# main.net
KiCad netlist of a schematic drawn in EAGLE
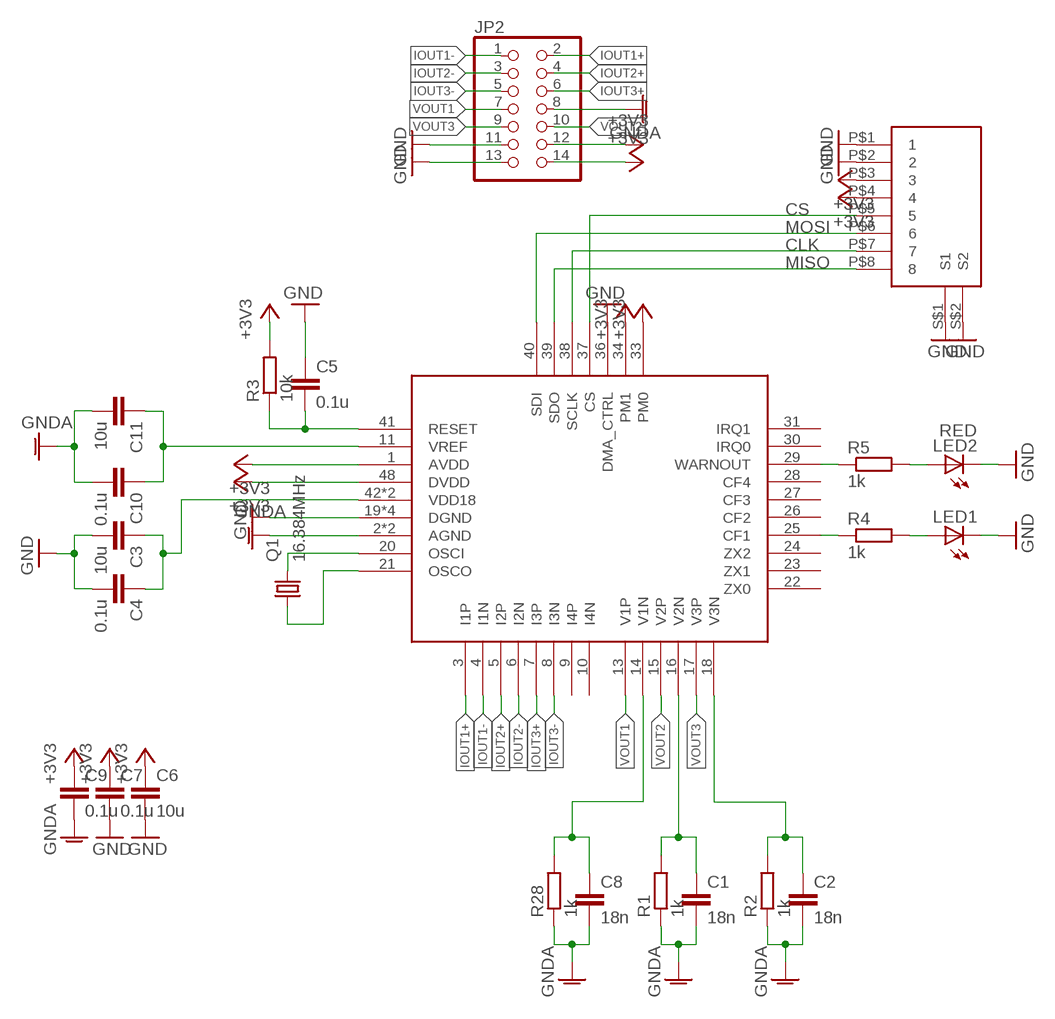
[diagram p0: schematic, sheet 1]

(export (version "E")
  (design (tool "Eeschema 10.0.6"))
  (components
    (comp (ref "C1")
      (value "18n")
      (footprint "eagle-import:C0805")
      (libsource (lib "eagle-import") (part "C-EUC0805"))
    )
    (comp (ref "C2")
      (value "18n")
      (footprint "eagle-import:C0805")
      (libsource (lib "eagle-import") (part "C-EUC0805"))
    )
    (comp (ref "C3")
      (value "10u")
      (footprint "eagle-import:C1206")
      (libsource (lib "eagle-import") (part "C-EUC1206"))
    )
    (comp (ref "C4")
      (value "0.1u")
      (footprint "eagle-import:C0805")
      (libsource (lib "eagle-import") (part "C-EUC0805"))
    )
    (comp (ref "C5")
      (value "0.1u")
      (footprint "eagle-import:C0805")
      (libsource (lib "eagle-import") (part "C-EUC0805"))
    )
    (comp (ref "C6")
      (value "10u")
      (footprint "eagle-import:C1206")
      (libsource (lib "eagle-import") (part "C-EUC1206"))
    )
    (comp (ref "C7")
      (value "0.1u")
      (footprint "eagle-import:C0805")
      (libsource (lib "eagle-import") (part "C-EUC0805"))
    )
    (comp (ref "C8")
      (value "18n")
      (footprint "eagle-import:C0805")
      (libsource (lib "eagle-import") (part "C-EUC0805"))
    )
    (comp (ref "C9")
      (value "0.1u")
      (footprint "eagle-import:C0805")
      (libsource (lib "eagle-import") (part "C-EUC0805"))
    )
    (comp (ref "C10")
      (value "0.1u")
      (footprint "eagle-import:C0805")
      (libsource (lib "eagle-import") (part "C-EUC0805"))
    )
    (comp (ref "C11")
      (value "10u")
      (footprint "eagle-import:C0805")
      (libsource (lib "eagle-import") (part "C-EUC0805"))
    )
    (comp (ref "C12")
      (value "RJ45-ASSMANN")
      (footprint "eagle-import:RJ45-ASSMANN")
      (libsource (lib "eagle-import") (part "RJ45-ASSMANN"))
    )
    (comp (ref "JP2")
      (value "PINHD-2X7")
      (footprint "eagle-import:2X07")
      (libsource (lib "eagle-import") (part "PINHD-2X7"))
    )
    (comp (ref "LED1")
      (value "LEDCHIPLED_1206")
      (footprint "eagle-import:CHIPLED_1206")
      (libsource (lib "eagle-import") (part "LEDCHIPLED_1206"))
    )
    (comp (ref "LED2")
      (value "RED")
      (footprint "eagle-import:CHIPLED_1206")
      (libsource (lib "eagle-import") (part "LEDCHIPLED_1206"))
    )
    (comp (ref "Q1")
      (value "16.384MHz")
      (footprint "eagle-import:5.0X3.2_KX-9A")
      (libsource (lib "eagle-import") (part "KX-9A"))
    )
    (comp (ref "R1")
      (value "1k")
      (footprint "eagle-import:M0805")
      (libsource (lib "eagle-import") (part "R-EU_M0805"))
    )
    (comp (ref "R2")
      (value "1k")
      (footprint "eagle-import:M0805")
      (libsource (lib "eagle-import") (part "R-EU_M0805"))
    )
    (comp (ref "R3")
      (value "10k")
      (footprint "eagle-import:M0805")
      (libsource (lib "eagle-import") (part "R-EU_M0805"))
    )
    (comp (ref "R4")
      (value "1k")
      (footprint "eagle-import:R0805")
      (libsource (lib "eagle-import") (part "R-EU_R0805"))
    )
    (comp (ref "R5")
      (value "1k")
      (footprint "eagle-import:R0805")
      (libsource (lib "eagle-import") (part "R-EU_R0805"))
    )
    (comp (ref "R28")
      (value "1k")
      (footprint "eagle-import:M0805")
      (libsource (lib "eagle-import") (part "R-EU_M0805"))
    )
    (comp (ref "U$1")
      (value "ATM90E36A")
      (footprint "eagle-import:QFP50P900X900X120-48")
      (libsource (lib "eagle-import") (part "ATM90E36A"))
    )
  )
  (nets
    (net (code "1") (name "+3V3") (class "Default")
      (node (ref "C12") (pin "P$3") (pinfunction "3_P$3") (pintype "bidirectional"))
      (node (ref "C12") (pin "P$4") (pinfunction "4_P$4") (pintype "bidirectional"))
      (node (ref "C6") (pin "1") (pinfunction "1_1") (pintype "passive"))
      (node (ref "C7") (pin "1") (pinfunction "1_1") (pintype "passive"))
      (node (ref "C9") (pin "1") (pinfunction "1_1") (pintype "passive"))
      (node (ref "JP2") (pin "12") (pinfunction "12_12") (pintype "passive"))
      (node (ref "JP2") (pin "14") (pinfunction "14_14") (pintype "passive"))
      (node (ref "R3") (pin "2") (pinfunction "2_2") (pintype "passive"))
      (node (ref "U$1") (pin "1") (pinfunction "AVDD_1") (pintype "bidirectional"))
      (node (ref "U$1") (pin "33") (pinfunction "PM0_33") (pintype "bidirectional"))
      (node (ref "U$1") (pin "34") (pinfunction "PM1_34") (pintype "bidirectional"))
      (node (ref "U$1") (pin "48") (pinfunction "DVDD_48") (pintype "bidirectional"))
    )
    (net (code "2") (name "/CLK") (class "Default")
      (node (ref "C12") (pin "P$7") (pinfunction "7_P$7") (pintype "bidirectional"))
      (node (ref "U$1") (pin "38") (pinfunction "SCLK_38") (pintype "bidirectional"))
    )
    (net (code "3") (name "/CS") (class "Default")
      (node (ref "C12") (pin "P$5") (pinfunction "5_P$5") (pintype "bidirectional"))
      (node (ref "U$1") (pin "37") (pinfunction "CS_37") (pintype "bidirectional"))
    )
    (net (code "4") (name "/MISO") (class "Default")
      (node (ref "C12") (pin "P$8") (pinfunction "8_P$8") (pintype "bidirectional"))
      (node (ref "U$1") (pin "39") (pinfunction "SDO_39") (pintype "bidirectional"))
    )
    (net (code "5") (name "/MOSI") (class "Default")
      (node (ref "C12") (pin "P$6") (pinfunction "6_P$6") (pintype "bidirectional"))
      (node (ref "U$1") (pin "40") (pinfunction "SDI_40") (pintype "bidirectional"))
    )
    (net (code "6") (name "GND") (class "Default")
      (node (ref "C12") (pin "P$1") (pinfunction "1_P$1") (pintype "bidirectional"))
      (node (ref "C12") (pin "P$2") (pinfunction "2_P$2") (pintype "bidirectional"))
      (node (ref "C12") (pin "S$1") (pinfunction "S1_S$1") (pintype "bidirectional"))
      (node (ref "C12") (pin "S$2") (pinfunction "S2_S$2") (pintype "bidirectional"))
      (node (ref "C3") (pin "2") (pinfunction "2_2") (pintype "passive"))
      (node (ref "C4") (pin "2") (pinfunction "2_2") (pintype "passive"))
      (node (ref "C5") (pin "1") (pinfunction "1_1") (pintype "passive"))
      (node (ref "C6") (pin "2") (pinfunction "2_2") (pintype "passive"))
      (node (ref "C7") (pin "2") (pinfunction "2_2") (pintype "passive"))
      (node (ref "JP2") (pin "11") (pinfunction "11_11") (pintype "passive"))
      (node (ref "JP2") (pin "13") (pinfunction "13_13") (pintype "passive"))
      (node (ref "LED1") (pin "C") (pinfunction "C_C") (pintype "passive"))
      (node (ref "LED2") (pin "C") (pinfunction "C_C") (pintype "passive"))
      (node (ref "U$1") (pin "19") (pinfunction "DGND_19") (pintype "bidirectional"))
      (node (ref "U$1") (pin "32") (pinfunction "DGND_32") (pintype "bidirectional"))
      (node (ref "U$1") (pin "36") (pinfunction "DMA_CTRL_36") (pintype "bidirectional"))
      (node (ref "U$1") (pin "44") (pinfunction "DGND_44") (pintype "bidirectional"))
      (node (ref "U$1") (pin "47") (pinfunction "DGND_47") (pintype "bidirectional"))
    )
    (net (code "7") (name "GNDA") (class "Default")
      (node (ref "C1") (pin "2") (pinfunction "2_2") (pintype "passive"))
      (node (ref "C10") (pin "2") (pinfunction "2_2") (pintype "passive"))
      (node (ref "C11") (pin "2") (pinfunction "2_2") (pintype "passive"))
      (node (ref "C2") (pin "2") (pinfunction "2_2") (pintype "passive"))
      (node (ref "C8") (pin "2") (pinfunction "2_2") (pintype "passive"))
      (node (ref "C9") (pin "2") (pinfunction "2_2") (pintype "passive"))
      (node (ref "JP2") (pin "8") (pinfunction "8_8") (pintype "passive"))
      (node (ref "R1") (pin "1") (pinfunction "1_1") (pintype "passive"))
      (node (ref "R2") (pin "1") (pinfunction "1_1") (pintype "passive"))
      (node (ref "R28") (pin "1") (pinfunction "1_1") (pintype "passive"))
      (node (ref "U$1") (pin "12") (pinfunction "AGND_12") (pintype "bidirectional"))
      (node (ref "U$1") (pin "2") (pinfunction "AGND_2") (pintype "bidirectional"))
    )
    (net (code "8") (name "IOUT1+") (class "Default")
      (node (ref "JP2") (pin "2") (pinfunction "2_2") (pintype "passive"))
      (node (ref "U$1") (pin "3") (pinfunction "I1P_3") (pintype "bidirectional"))
    )
    (net (code "9") (name "IOUT1-") (class "Default")
      (node (ref "JP2") (pin "1") (pinfunction "1_1") (pintype "passive"))
      (node (ref "U$1") (pin "4") (pinfunction "I1N_4") (pintype "bidirectional"))
    )
    (net (code "10") (name "IOUT2+") (class "Default")
      (node (ref "JP2") (pin "4") (pinfunction "4_4") (pintype "passive"))
      (node (ref "U$1") (pin "5") (pinfunction "I2P_5") (pintype "bidirectional"))
    )
    (net (code "11") (name "IOUT2-") (class "Default")
      (node (ref "JP2") (pin "3") (pinfunction "3_3") (pintype "passive"))
      (node (ref "U$1") (pin "6") (pinfunction "I2N_6") (pintype "bidirectional"))
    )
    (net (code "12") (name "IOUT3+") (class "Default")
      (node (ref "JP2") (pin "6") (pinfunction "6_6") (pintype "passive"))
      (node (ref "U$1") (pin "7") (pinfunction "I3P_7") (pintype "bidirectional"))
    )
    (net (code "13") (name "IOUT3-") (class "Default")
      (node (ref "JP2") (pin "5") (pinfunction "5_5") (pintype "passive"))
      (node (ref "U$1") (pin "8") (pinfunction "I3N_8") (pintype "bidirectional"))
    )
    (net (code "14") (name "Net-(C3-Pad1)") (class "Default")
      (node (ref "C3") (pin "1") (pinfunction "1_1") (pintype "passive"))
      (node (ref "C4") (pin "1") (pinfunction "1_1") (pintype "passive"))
      (node (ref "U$1") (pin "42") (pinfunction "VDD18_42") (pintype "bidirectional"))
      (node (ref "U$1") (pin "43") (pinfunction "VDD18_43") (pintype "bidirectional"))
    )
    (net (code "15") (name "Net-(LED1-PadA)") (class "Default")
      (node (ref "LED1") (pin "A") (pinfunction "A_A") (pintype "passive"))
      (node (ref "R4") (pin "2") (pinfunction "2_2") (pintype "passive"))
    )
    (net (code "16") (name "Net-(LED2-PadA)") (class "Default")
      (node (ref "LED2") (pin "A") (pinfunction "A_A") (pintype "passive"))
      (node (ref "R5") (pin "2") (pinfunction "2_2") (pintype "passive"))
    )
    (net (code "17") (name "Net-(Q1-2)") (class "Default")
      (node (ref "Q1") (pin "3") (pinfunction "2_3") (pintype "passive"))
      (node (ref "U$1") (pin "20") (pinfunction "OSCI_20") (pintype "bidirectional"))
    )
    (net (code "18") (name "Net-(U$1-CF1)") (class "Default")
      (node (ref "R4") (pin "1") (pinfunction "1_1") (pintype "passive"))
      (node (ref "U$1") (pin "25") (pinfunction "CF1_25") (pintype "bidirectional"))
    )
    (net (code "19") (name "Net-(U$1-OSCO)") (class "Default")
      (node (ref "Q1") (pin "1") (pinfunction "1_1") (pintype "passive"))
      (node (ref "U$1") (pin "21") (pinfunction "OSCO_21") (pintype "bidirectional"))
    )
    (net (code "20") (name "Net-(U$1-RESET)") (class "Default")
      (node (ref "C5") (pin "2") (pinfunction "2_2") (pintype "passive"))
      (node (ref "R3") (pin "1") (pinfunction "1_1") (pintype "passive"))
      (node (ref "U$1") (pin "41") (pinfunction "RESET_41") (pintype "bidirectional"))
    )
    (net (code "21") (name "Net-(U$1-V1N)") (class "Default")
      (node (ref "C8") (pin "1") (pinfunction "1_1") (pintype "passive"))
      (node (ref "R28") (pin "2") (pinfunction "2_2") (pintype "passive"))
      (node (ref "U$1") (pin "14") (pinfunction "V1N_14") (pintype "bidirectional"))
    )
    (net (code "22") (name "Net-(U$1-V2N)") (class "Default")
      (node (ref "C1") (pin "1") (pinfunction "1_1") (pintype "passive"))
      (node (ref "R1") (pin "2") (pinfunction "2_2") (pintype "passive"))
      (node (ref "U$1") (pin "16") (pinfunction "V2N_16") (pintype "bidirectional"))
    )
    (net (code "23") (name "Net-(U$1-V3N)") (class "Default")
      (node (ref "C2") (pin "1") (pinfunction "1_1") (pintype "passive"))
      (node (ref "R2") (pin "2") (pinfunction "2_2") (pintype "passive"))
      (node (ref "U$1") (pin "18") (pinfunction "V3N_18") (pintype "bidirectional"))
    )
    (net (code "24") (name "Net-(U$1-VREF)") (class "Default")
      (node (ref "C10") (pin "1") (pinfunction "1_1") (pintype "passive"))
      (node (ref "C11") (pin "1") (pinfunction "1_1") (pintype "passive"))
      (node (ref "U$1") (pin "11") (pinfunction "VREF_11") (pintype "bidirectional"))
    )
    (net (code "25") (name "Net-(U$1-WARNOUT)") (class "Default")
      (node (ref "R5") (pin "1") (pinfunction "1_1") (pintype "passive"))
      (node (ref "U$1") (pin "29") (pinfunction "WARNOUT_29") (pintype "bidirectional"))
    )
    (net (code "26") (name "VOUT1") (class "Default")
      (node (ref "JP2") (pin "7") (pinfunction "7_7") (pintype "passive"))
      (node (ref "U$1") (pin "13") (pinfunction "V1P_13") (pintype "bidirectional"))
    )
    (net (code "27") (name "VOUT2") (class "Default")
      (node (ref "JP2") (pin "10") (pinfunction "10_10") (pintype "passive"))
      (node (ref "U$1") (pin "15") (pinfunction "V2P_15") (pintype "bidirectional"))
    )
    (net (code "28") (name "VOUT3") (class "Default")
      (node (ref "JP2") (pin "9") (pinfunction "9_9") (pintype "passive"))
      (node (ref "U$1") (pin "17") (pinfunction "V3P_17") (pintype "bidirectional"))
    )
    (net (code "29") (name "unconnected-(U$1-CF2-Pad26)") (class "Default")
      (node (ref "U$1") (pin "26") (pinfunction "CF2_26") (pintype "bidirectional"))
    )
    (net (code "30") (name "unconnected-(U$1-CF3-Pad27)") (class "Default")
      (node (ref "U$1") (pin "27") (pinfunction "CF3_27") (pintype "bidirectional"))
    )
    (net (code "31") (name "unconnected-(U$1-CF4-Pad28)") (class "Default")
      (node (ref "U$1") (pin "28") (pinfunction "CF4_28") (pintype "bidirectional"))
    )
    (net (code "32") (name "unconnected-(U$1-I4N-Pad10)") (class "Default")
      (node (ref "U$1") (pin "10") (pinfunction "I4N_10") (pintype "bidirectional"))
    )
    (net (code "33") (name "unconnected-(U$1-I4P-Pad9)") (class "Default")
      (node (ref "U$1") (pin "9") (pinfunction "I4P_9") (pintype "bidirectional"))
    )
    (net (code "34") (name "unconnected-(U$1-IRQ0-Pad30)") (class "Default")
      (node (ref "U$1") (pin "30") (pinfunction "IRQ0_30") (pintype "bidirectional"))
    )
    (net (code "35") (name "unconnected-(U$1-IRQ1-Pad31)") (class "Default")
      (node (ref "U$1") (pin "31") (pinfunction "IRQ1_31") (pintype "bidirectional"))
    )
    (net (code "36") (name "unconnected-(U$1-ZX0-Pad22)") (class "Default")
      (node (ref "U$1") (pin "22") (pinfunction "ZX0_22") (pintype "bidirectional"))
    )
    (net (code "37") (name "unconnected-(U$1-ZX1-Pad23)") (class "Default")
      (node (ref "U$1") (pin "23") (pinfunction "ZX1_23") (pintype "bidirectional"))
    )
    (net (code "38") (name "unconnected-(U$1-ZX2-Pad24)") (class "Default")
      (node (ref "U$1") (pin "24") (pinfunction "ZX2_24") (pintype "bidirectional"))
    )
  )
)
